# cryocooler_phase_lock.net
KiCad netlist of a schematic drawn in EAGLE
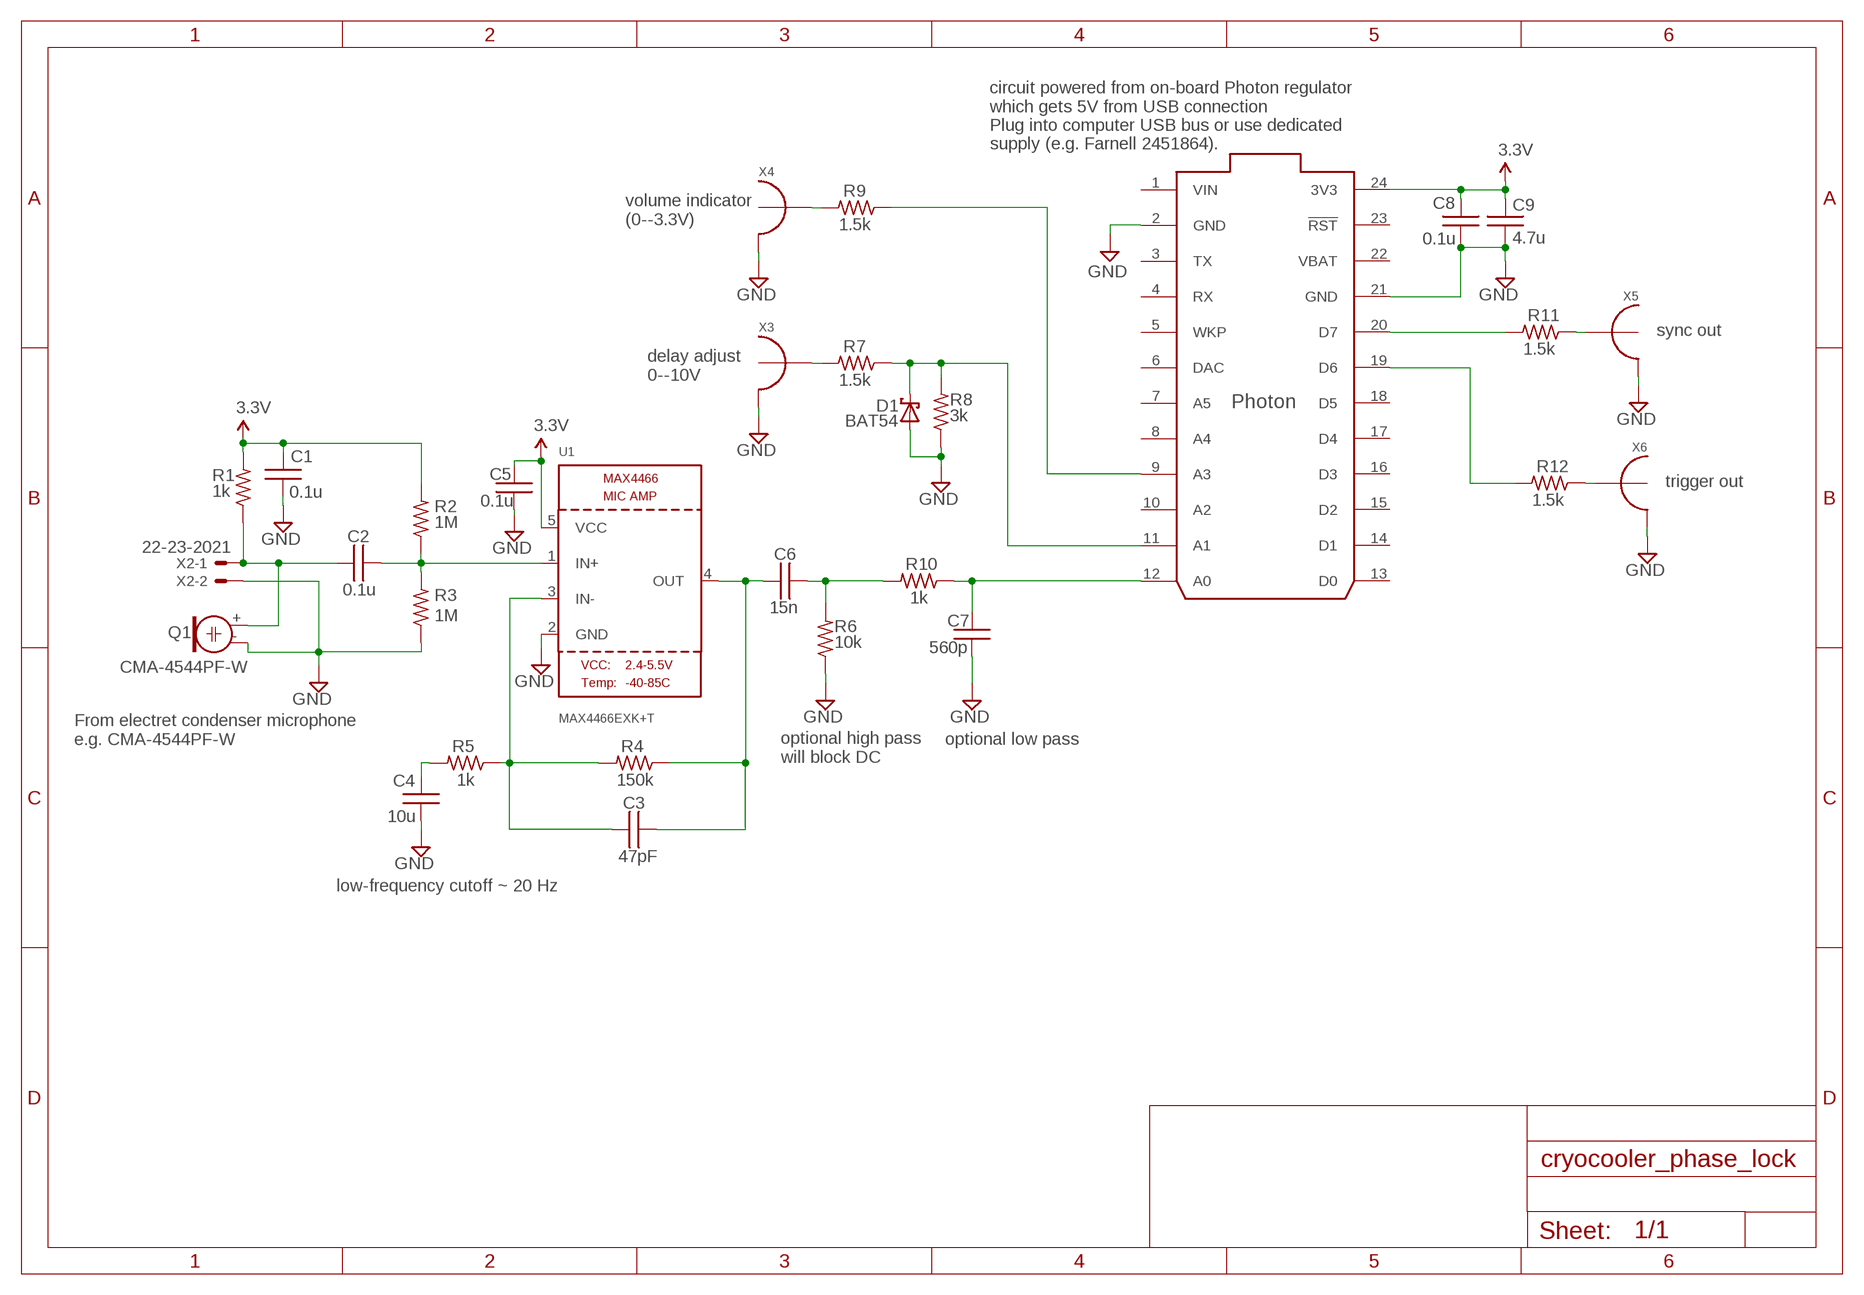
[diagram p0: schematic, sheet 1]

(export (version "E")
  (design (tool "Eeschema 10.0.6"))
  (components
    (comp (ref "C1")
      (value "0.1u")
      (footprint "eagle-import:0603")
      (libsource (lib "eagle-import") (part "C0603"))
    )
    (comp (ref "C2")
      (value "0.1u")
      (footprint "eagle-import:0603")
      (libsource (lib "eagle-import") (part "C0603"))
    )
    (comp (ref "C3")
      (value "47pF")
      (footprint "eagle-import:0603")
      (libsource (lib "eagle-import") (part "C0603"))
    )
    (comp (ref "C4")
      (value "10u")
      (footprint "eagle-import:0603")
      (libsource (lib "eagle-import") (part "C0603"))
    )
    (comp (ref "C5")
      (value "0.1u")
      (footprint "eagle-import:0603")
      (libsource (lib "eagle-import") (part "C0603"))
    )
    (comp (ref "C6")
      (value "15n")
      (footprint "eagle-import:0603")
      (libsource (lib "eagle-import") (part "C0603"))
    )
    (comp (ref "C7")
      (value "560p")
      (footprint "eagle-import:0603")
      (libsource (lib "eagle-import") (part "C0603"))
    )
    (comp (ref "C8")
      (value "0.1u")
      (footprint "eagle-import:0603")
      (libsource (lib "eagle-import") (part "C0603"))
    )
    (comp (ref "C9")
      (value "4.7u")
      (footprint "eagle-import:0805")
      (libsource (lib "eagle-import") (part "C0805"))
    )
    (comp (ref "D1")
      (value "BAT54")
      (footprint "eagle-import:SOT23")
      (libsource (lib "eagle-import") (part "BAT54"))
    )
    (comp (ref "Q1")
      (value "CMA-4544PF-W")
      (footprint "eagle-import:ELECTRET_9.7")
      (libsource (lib "eagle-import") (part "ELECTRET"))
    )
    (comp (ref "R1")
      (value "1k")
      (footprint "eagle-import:0603")
      (libsource (lib "eagle-import") (part "R0603"))
    )
    (comp (ref "R2")
      (value "1M")
      (footprint "eagle-import:0603")
      (libsource (lib "eagle-import") (part "R0603"))
    )
    (comp (ref "R3")
      (value "1M")
      (footprint "eagle-import:0603")
      (libsource (lib "eagle-import") (part "R0603"))
    )
    (comp (ref "R4")
      (value "150k")
      (footprint "eagle-import:0603")
      (libsource (lib "eagle-import") (part "R0603"))
    )
    (comp (ref "R5")
      (value "1k")
      (footprint "eagle-import:0603")
      (libsource (lib "eagle-import") (part "R0603"))
    )
    (comp (ref "R6")
      (value "10k")
      (footprint "eagle-import:0603")
      (libsource (lib "eagle-import") (part "R0603"))
    )
    (comp (ref "R7")
      (value "1.5k")
      (footprint "eagle-import:0603")
      (libsource (lib "eagle-import") (part "R0603"))
    )
    (comp (ref "R8")
      (value "3k")
      (footprint "eagle-import:0603")
      (libsource (lib "eagle-import") (part "R0603"))
    )
    (comp (ref "R9")
      (value "1.5k")
      (footprint "eagle-import:0603")
      (libsource (lib "eagle-import") (part "R0603"))
    )
    (comp (ref "R10")
      (value "1k")
      (footprint "eagle-import:0603")
      (libsource (lib "eagle-import") (part "R0603"))
    )
    (comp (ref "R11")
      (value "1.5k")
      (footprint "eagle-import:0603")
      (libsource (lib "eagle-import") (part "R0603"))
    )
    (comp (ref "R12")
      (value "1.5k")
      (footprint "eagle-import:0603")
      (libsource (lib "eagle-import") (part "R0603"))
    )
    (comp (ref "U1")
      (value "MAX4466EXK+T")
      (footprint "eagle-import:SC70-5")
      (libsource (lib "eagle-import") (part "MAX4466{dblquote}{dblquote}"))
    )
    (comp (ref "U3")
      (value "PHOTON_WITH_HEADERS")
      (footprint "eagle-import:PHOTON")
      (libsource (lib "eagle-import") (part "PHOTON_WITH_HEADERS"))
    )
    (comp (ref "X2")
      (value "22-23-2021")
      (footprint "eagle-import:22-23-2021")
      (fields (field (name "MF") "MOLEX"))
      (libsource (lib "eagle-import") (part "22-23-2021"))
    )
    (comp (ref "X3")
      (value "BNC_VERTICAL")
      (footprint "eagle-import:BNC_VERTICAL")
      (libsource (lib "eagle-import") (part "BNC_VERTICAL"))
    )
    (comp (ref "X4")
      (value "BNC_VERTICAL")
      (footprint "eagle-import:BNC_VERTICAL")
      (libsource (lib "eagle-import") (part "BNC_VERTICAL"))
    )
    (comp (ref "X5")
      (value "BNC_VERTICAL")
      (footprint "eagle-import:BNC_VERTICAL")
      (libsource (lib "eagle-import") (part "BNC_VERTICAL"))
    )
    (comp (ref "X6")
      (value "BNC_VERTICAL")
      (footprint "eagle-import:BNC_VERTICAL")
      (libsource (lib "eagle-import") (part "BNC_VERTICAL"))
    )
  )
  (nets
    (net (code "1") (name "/VBAT") (class "Default")
      (node (ref "U3") (pin "22") (pinfunction "VBAT_22") (pintype "power_in"))
    )
    (net (code "2") (name "/VIN") (class "Default")
      (node (ref "U3") (pin "1") (pinfunction "VIN_1") (pintype "power_in"))
    )
    (net (code "3") (name "3.3V") (class "Default")
      (node (ref "C1") (pin "1") (pinfunction "1_1") (pintype "passive"))
      (node (ref "C5") (pin "1") (pinfunction "1_1") (pintype "passive"))
      (node (ref "C8") (pin "1") (pinfunction "1_1") (pintype "passive"))
      (node (ref "C9") (pin "2") (pinfunction "2_2") (pintype "passive"))
      (node (ref "R1") (pin "2") (pinfunction "2_2") (pintype "passive"))
      (node (ref "R2") (pin "2") (pinfunction "2_2") (pintype "passive"))
      (node (ref "U1") (pin "5") (pinfunction "VCC_5") (pintype "bidirectional"))
      (node (ref "U3") (pin "24") (pinfunction "3V3_24") (pintype "power_in"))
    )
    (net (code "4") (name "GND") (class "Default")
      (node (ref "C1") (pin "2") (pinfunction "2_2") (pintype "passive"))
      (node (ref "C4") (pin "2") (pinfunction "2_2") (pintype "passive"))
      (node (ref "C5") (pin "2") (pinfunction "2_2") (pintype "passive"))
      (node (ref "C7") (pin "2") (pinfunction "2_2") (pintype "passive"))
      (node (ref "C8") (pin "2") (pinfunction "2_2") (pintype "passive"))
      (node (ref "C9") (pin "1") (pinfunction "1_1") (pintype "passive"))
      (node (ref "D1") (pin "1") (pinfunction "A_1") (pintype "passive"))
      (node (ref "Q1") (pin "-") (pinfunction "1_-") (pintype "passive"))
      (node (ref "R3") (pin "1") (pinfunction "1_1") (pintype "passive"))
      (node (ref "R6") (pin "1") (pinfunction "1_1") (pintype "passive"))
      (node (ref "R8") (pin "1") (pinfunction "1_1") (pintype "passive"))
      (node (ref "U1") (pin "2") (pinfunction "GND_2") (pintype "bidirectional"))
      (node (ref "U3") (pin "2") (pinfunction "GND_2") (pintype "power_in"))
      (node (ref "U3") (pin "21") (pinfunction "GND_21") (pintype "power_in"))
      (node (ref "X2") (pin "2") (pinfunction "S_2") (pintype "passive"))
      (node (ref "X3") (pin "GND") (pinfunction "GND_GND") (pintype "bidirectional"))
      (node (ref "X4") (pin "GND") (pinfunction "GND_GND") (pintype "bidirectional"))
      (node (ref "X5") (pin "GND") (pinfunction "GND_GND") (pintype "bidirectional"))
      (node (ref "X6") (pin "GND") (pinfunction "GND_GND") (pintype "bidirectional"))
    )
    (net (code "5") (name "Net-(C4-Pad1)") (class "Default")
      (node (ref "C4") (pin "1") (pinfunction "1_1") (pintype "passive"))
      (node (ref "R5") (pin "2") (pinfunction "2_2") (pintype "passive"))
    )
    (net (code "6") (name "Net-(C6-Pad2)") (class "Default")
      (node (ref "C6") (pin "2") (pinfunction "2_2") (pintype "passive"))
      (node (ref "R10") (pin "2") (pinfunction "2_2") (pintype "passive"))
      (node (ref "R6") (pin "2") (pinfunction "2_2") (pintype "passive"))
    )
    (net (code "7") (name "Net-(D1-C)") (class "Default")
      (node (ref "D1") (pin "3") (pinfunction "C_3") (pintype "passive"))
      (node (ref "R7") (pin "1") (pinfunction "1_1") (pintype "passive"))
      (node (ref "R8") (pin "2") (pinfunction "2_2") (pintype "passive"))
      (node (ref "U3") (pin "11") (pinfunction "A1_11") (pintype "bidirectional"))
    )
    (net (code "8") (name "Net-(Q1-2)") (class "Default")
      (node (ref "C2") (pin "1") (pinfunction "1_1") (pintype "passive"))
      (node (ref "Q1") (pin "+") (pinfunction "2_+") (pintype "passive"))
      (node (ref "R1") (pin "1") (pinfunction "1_1") (pintype "passive"))
      (node (ref "X2") (pin "1") (pinfunction "S_1") (pintype "passive"))
    )
    (net (code "9") (name "Net-(R7-Pad2)") (class "Default")
      (node (ref "R7") (pin "2") (pinfunction "2_2") (pintype "passive"))
      (node (ref "X3") (pin "SIGNAL") (pinfunction "SIGNAL_SIGNAL") (pintype "bidirectional"))
    )
    (net (code "10") (name "Net-(R9-Pad2)") (class "Default")
      (node (ref "R9") (pin "2") (pinfunction "2_2") (pintype "passive"))
      (node (ref "X4") (pin "SIGNAL") (pinfunction "SIGNAL_SIGNAL") (pintype "bidirectional"))
    )
    (net (code "11") (name "Net-(R11-Pad1)") (class "Default")
      (node (ref "R11") (pin "1") (pinfunction "1_1") (pintype "passive"))
      (node (ref "X5") (pin "SIGNAL") (pinfunction "SIGNAL_SIGNAL") (pintype "bidirectional"))
    )
    (net (code "12") (name "Net-(R12-Pad1)") (class "Default")
      (node (ref "R12") (pin "1") (pinfunction "1_1") (pintype "passive"))
      (node (ref "X6") (pin "SIGNAL") (pinfunction "SIGNAL_SIGNAL") (pintype "bidirectional"))
    )
    (net (code "13") (name "Net-(U1-IN+)") (class "Default")
      (node (ref "C2") (pin "2") (pinfunction "2_2") (pintype "passive"))
      (node (ref "R2") (pin "1") (pinfunction "1_1") (pintype "passive"))
      (node (ref "R3") (pin "2") (pinfunction "2_2") (pintype "passive"))
      (node (ref "U1") (pin "1") (pinfunction "IN+_1") (pintype "bidirectional"))
    )
    (net (code "14") (name "Net-(U1-IN-)") (class "Default")
      (node (ref "C3") (pin "1") (pinfunction "1_1") (pintype "passive"))
      (node (ref "R4") (pin "2") (pinfunction "2_2") (pintype "passive"))
      (node (ref "R5") (pin "1") (pinfunction "1_1") (pintype "passive"))
      (node (ref "U1") (pin "3") (pinfunction "IN-_3") (pintype "bidirectional"))
    )
    (net (code "15") (name "Net-(U1-OUT)") (class "Default")
      (node (ref "C3") (pin "2") (pinfunction "2_2") (pintype "passive"))
      (node (ref "C6") (pin "1") (pinfunction "1_1") (pintype "passive"))
      (node (ref "R4") (pin "1") (pinfunction "1_1") (pintype "passive"))
      (node (ref "U1") (pin "4") (pinfunction "OUT_4") (pintype "bidirectional"))
    )
    (net (code "16") (name "Net-(U3-A0)") (class "Default")
      (node (ref "C7") (pin "1") (pinfunction "1_1") (pintype "passive"))
      (node (ref "R10") (pin "1") (pinfunction "1_1") (pintype "passive"))
      (node (ref "U3") (pin "12") (pinfunction "A0_12") (pintype "bidirectional"))
    )
    (net (code "17") (name "Net-(U3-A3)") (class "Default")
      (node (ref "R9") (pin "1") (pinfunction "1_1") (pintype "passive"))
      (node (ref "U3") (pin "9") (pinfunction "A3_9") (pintype "bidirectional"))
    )
    (net (code "18") (name "Net-(U3-D6)") (class "Default")
      (node (ref "R12") (pin "2") (pinfunction "2_2") (pintype "passive"))
      (node (ref "U3") (pin "19") (pinfunction "D6_19") (pintype "bidirectional"))
    )
    (net (code "19") (name "Net-(U3-D7)") (class "Default")
      (node (ref "R11") (pin "2") (pinfunction "2_2") (pintype "passive"))
      (node (ref "U3") (pin "20") (pinfunction "D7_20") (pintype "bidirectional"))
    )
    (net (code "20") (name "unconnected-(U3-A2-Pad10)") (class "Default")
      (node (ref "U3") (pin "10") (pinfunction "A2_10") (pintype "bidirectional"))
    )
    (net (code "21") (name "unconnected-(U3-A4-Pad8)") (class "Default")
      (node (ref "U3") (pin "8") (pinfunction "A4_8") (pintype "bidirectional"))
    )
    (net (code "22") (name "unconnected-(U3-A5-Pad7)") (class "Default")
      (node (ref "U3") (pin "7") (pinfunction "A5_7") (pintype "bidirectional"))
    )
    (net (code "23") (name "unconnected-(U3-D0-Pad13)") (class "Default")
      (node (ref "U3") (pin "13") (pinfunction "D0_13") (pintype "bidirectional"))
    )
    (net (code "24") (name "unconnected-(U3-D1-Pad14)") (class "Default")
      (node (ref "U3") (pin "14") (pinfunction "D1_14") (pintype "bidirectional"))
    )
    (net (code "25") (name "unconnected-(U3-D2-Pad15)") (class "Default")
      (node (ref "U3") (pin "15") (pinfunction "D2_15") (pintype "bidirectional"))
    )
    (net (code "26") (name "unconnected-(U3-D3-Pad16)") (class "Default")
      (node (ref "U3") (pin "16") (pinfunction "D3_16") (pintype "bidirectional"))
    )
    (net (code "27") (name "unconnected-(U3-D4-Pad17)") (class "Default")
      (node (ref "U3") (pin "17") (pinfunction "D4_17") (pintype "bidirectional"))
    )
    (net (code "28") (name "unconnected-(U3-D5-Pad18)") (class "Default")
      (node (ref "U3") (pin "18") (pinfunction "D5_18") (pintype "bidirectional"))
    )
    (net (code "29") (name "unconnected-(U3-DAC-Pad6)") (class "Default")
      (node (ref "U3") (pin "6") (pinfunction "DAC_6") (pintype "bidirectional"))
    )
    (net (code "30") (name "unconnected-(U3-RX-Pad4)") (class "Default")
      (node (ref "U3") (pin "4") (pinfunction "RX_4") (pintype "bidirectional"))
    )
    (net (code "31") (name "unconnected-(U3-TX-Pad3)") (class "Default")
      (node (ref "U3") (pin "3") (pinfunction "TX_3") (pintype "bidirectional"))
    )
    (net (code "32") (name "unconnected-(U3-WKP-Pad5)") (class "Default")
      (node (ref "U3") (pin "5") (pinfunction "WKP_5") (pintype "bidirectional"))
    )
    (net (code "33") (name "unconnected-(U3-~{RST}-Pad23)") (class "Default")
      (node (ref "U3") (pin "23") (pinfunction "~{RST}_23") (pintype "bidirectional"))
    )
  )
)
